# 7_cpu_powercon.net
KiCad netlist of a schematic drawn in EAGLE
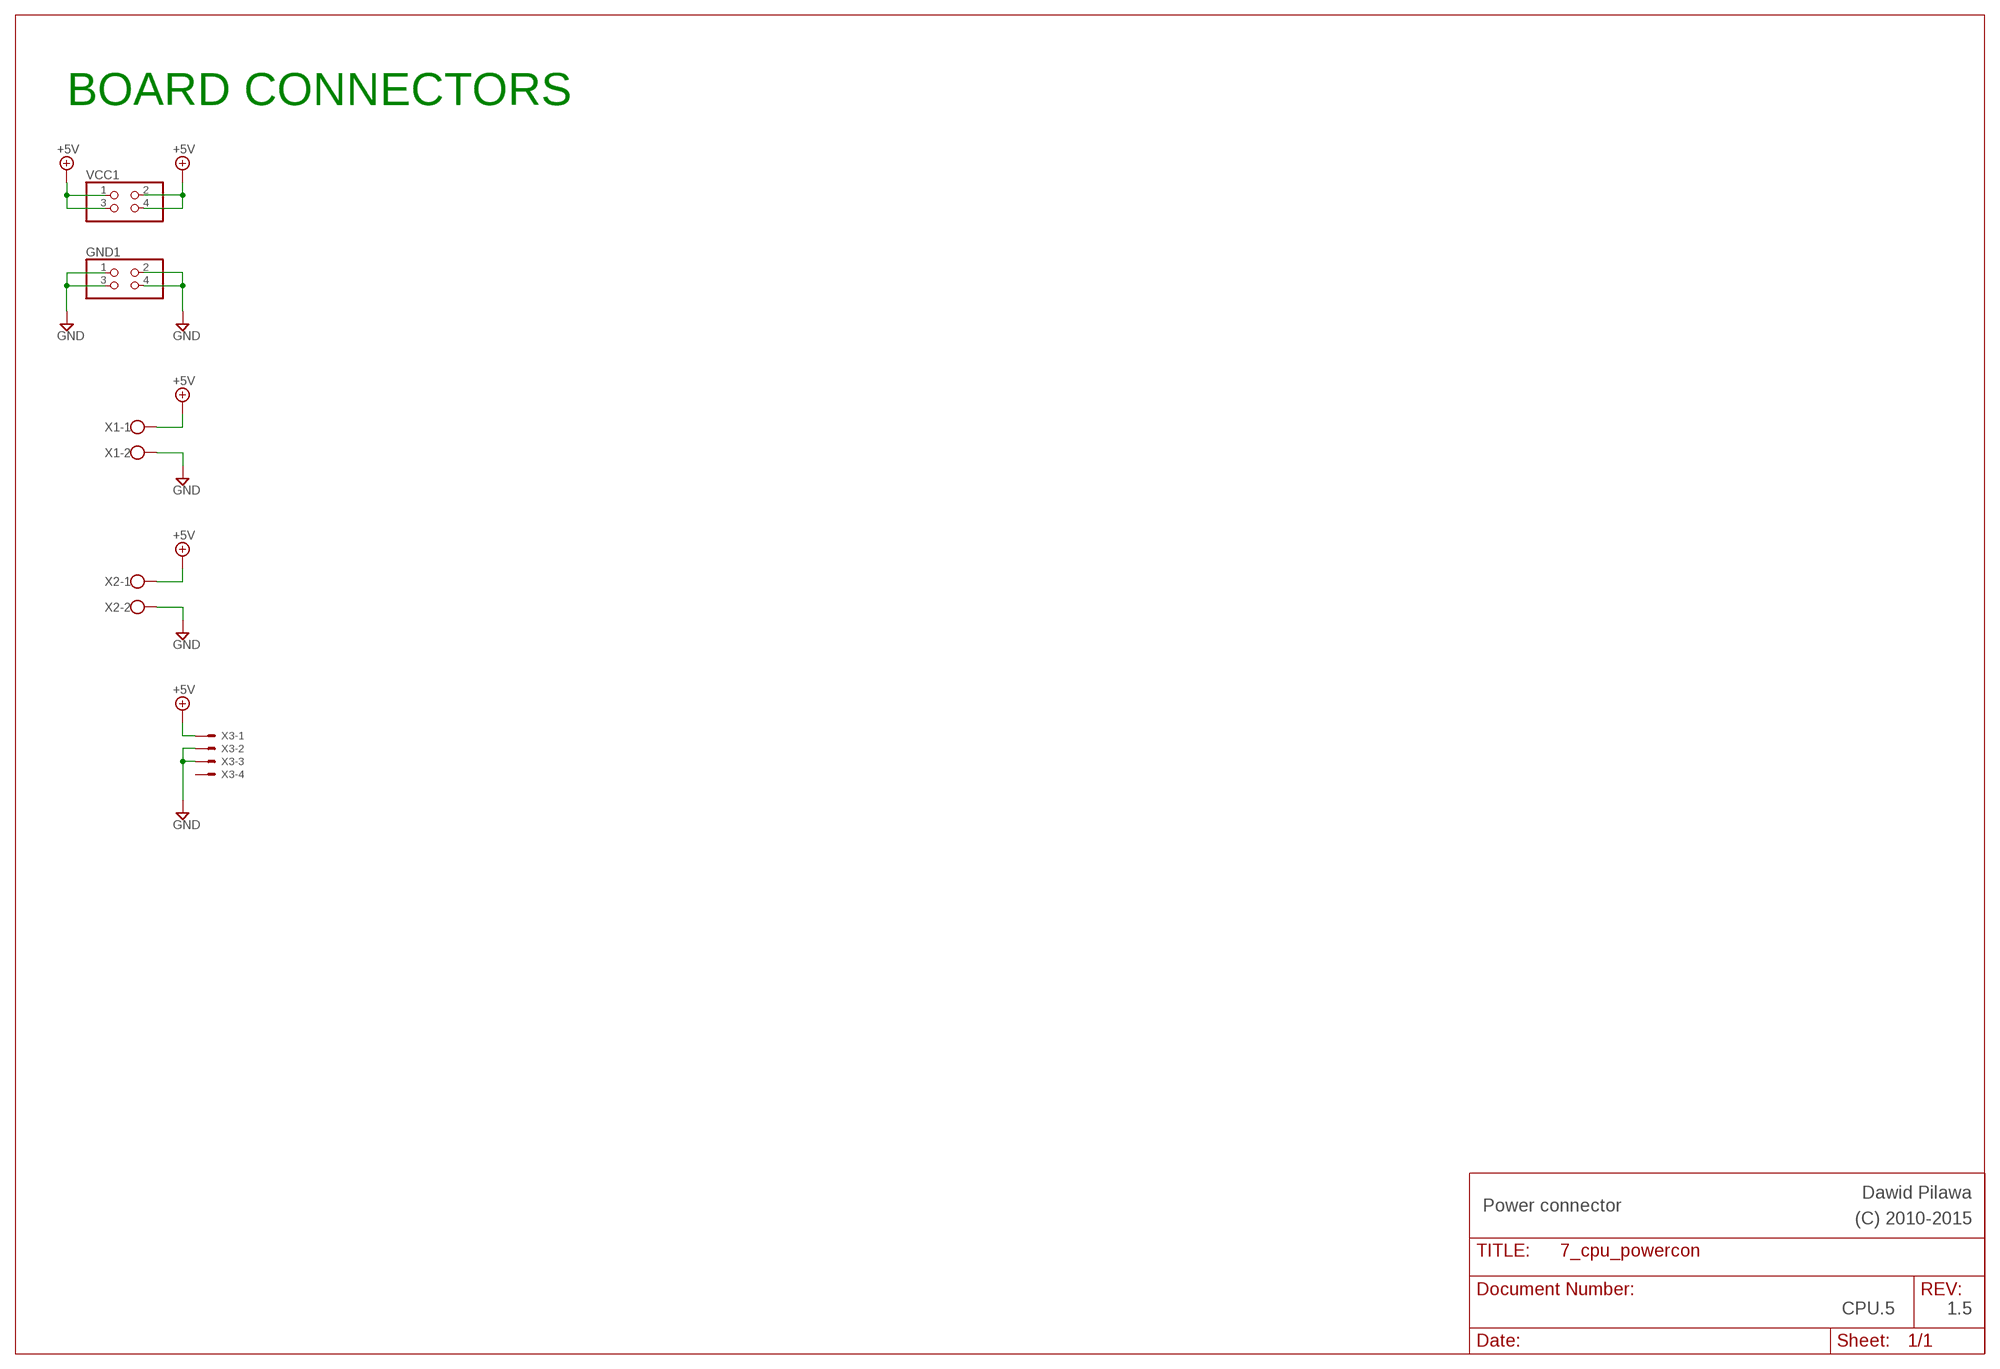
[diagram p0: schematic, sheet 1]

(export (version "E")
  (design (tool "Eeschema 10.0.6"))
  (components
    (comp (ref "GND1")
      (value "PINHD-2X2")
      (footprint "eagle-import:2X02")
      (libsource (lib "eagle-import") (part "PINHD-2X2"))
    )
    (comp (ref "VCC1")
      (value "PINHD-2X2")
      (footprint "eagle-import:2X02")
      (libsource (lib "eagle-import") (part "PINHD-2X2"))
    )
    (comp (ref "X1")
      (value "W237-102")
      (footprint "eagle-import:W237-102")
      (fields (field (name "MPN") "237-102"))
      (libsource (lib "eagle-import") (part "W237-102"))
    )
    (comp (ref "X2")
      (value "W237-102")
      (footprint "eagle-import:W237-102")
      (fields (field (name "MPN") "237-102"))
      (libsource (lib "eagle-import") (part "W237-102"))
    )
    (comp (ref "X3")
      (value "KK-156-4")
      (footprint "eagle-import:KK-156-4")
      (libsource (lib "eagle-import") (part "KK-156-4"))
    )
  )
  (nets
    (net (code "1") (name "+5V") (class "Default")
      (node (ref "VCC1") (pin "1") (pinfunction "1_1") (pintype "passive"))
      (node (ref "VCC1") (pin "2") (pinfunction "2_2") (pintype "passive"))
      (node (ref "VCC1") (pin "3") (pinfunction "3_3") (pintype "passive"))
      (node (ref "VCC1") (pin "4") (pinfunction "4_4") (pintype "passive"))
      (node (ref "X1") (pin "1") (pinfunction "KL_1") (pintype "passive"))
      (node (ref "X2") (pin "1") (pinfunction "KL_1") (pintype "passive"))
      (node (ref "X3") (pin "1") (pinfunction "S_1") (pintype "passive"))
    )
    (net (code "2") (name "GND") (class "Default")
      (node (ref "GND1") (pin "1") (pinfunction "1_1") (pintype "passive"))
      (node (ref "GND1") (pin "2") (pinfunction "2_2") (pintype "passive"))
      (node (ref "GND1") (pin "3") (pinfunction "3_3") (pintype "passive"))
      (node (ref "GND1") (pin "4") (pinfunction "4_4") (pintype "passive"))
      (node (ref "X1") (pin "2") (pinfunction "KL_2") (pintype "passive"))
      (node (ref "X2") (pin "2") (pinfunction "KL_2") (pintype "passive"))
      (node (ref "X3") (pin "2") (pinfunction "S_2") (pintype "passive"))
      (node (ref "X3") (pin "3") (pinfunction "S_3") (pintype "passive"))
    )
    (net (code "3") (name "unconnected-(X3D-S-Pad4)") (class "Default")
      (node (ref "X3") (pin "4") (pinfunction "S_4") (pintype "passive"))
    )
  )
)
